# DAC.net
KiCad netlist of a schematic drawn in Altium Designer
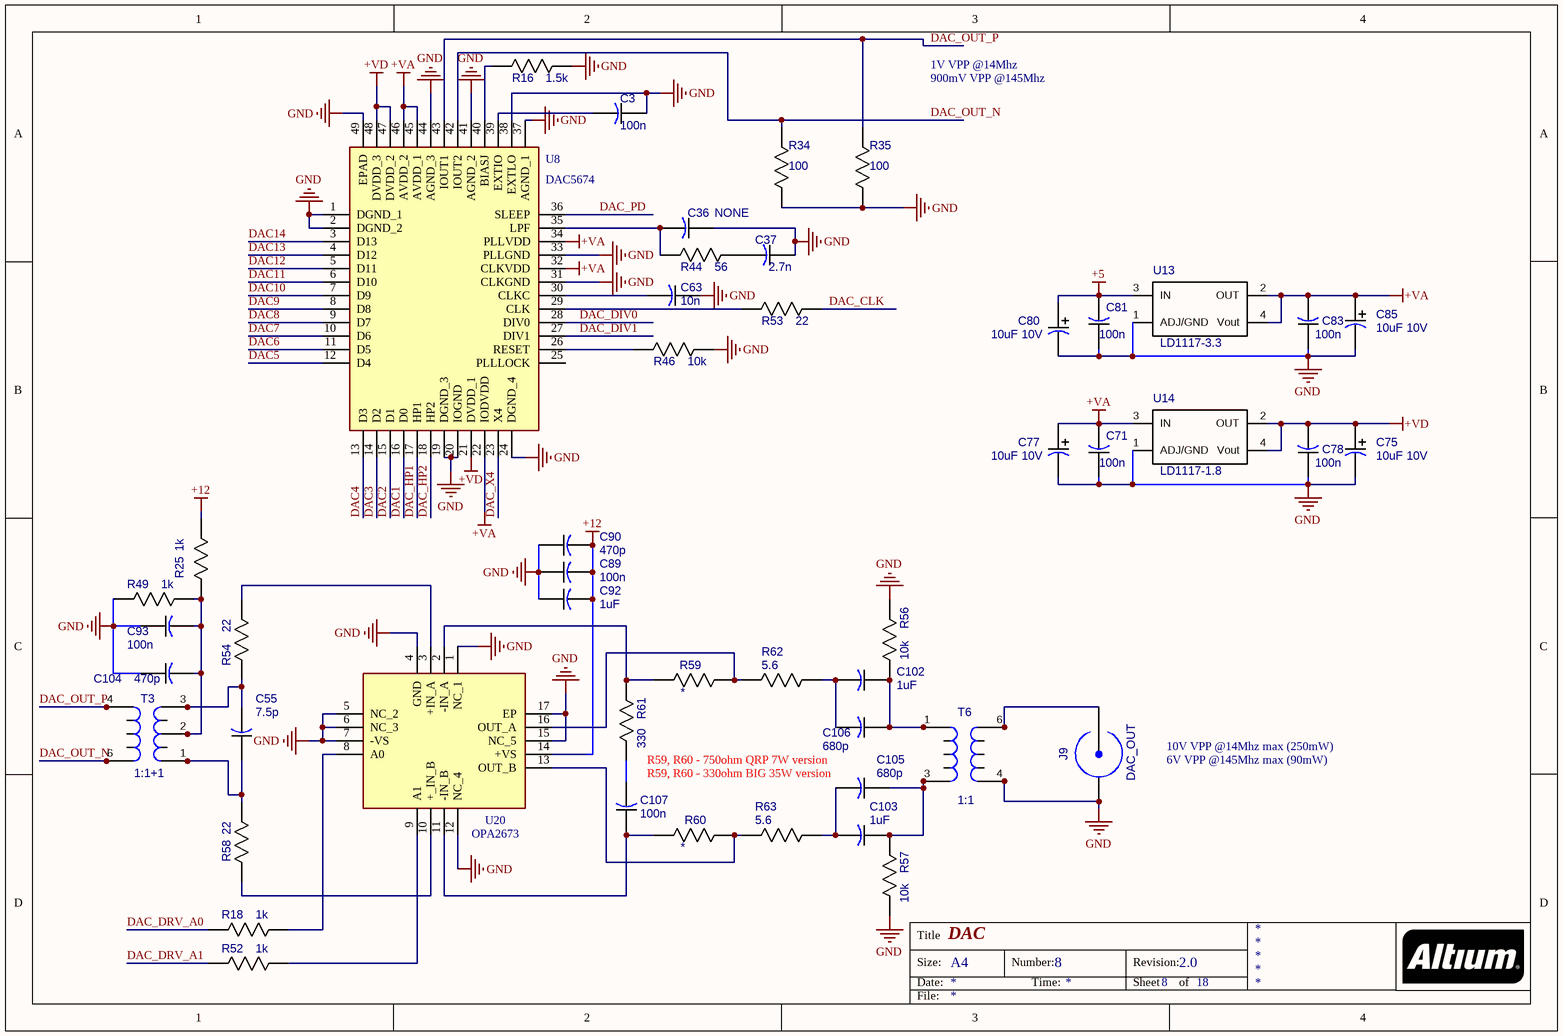
[diagram p0: DAC.SchDoc]

(export (version "E")
  (design (tool "Eeschema 10.0.6"))
  (components
    (comp (ref "C3")
      (value "100n")
      (footprint "CAP_0805")
      (description "CAP_0805")
      (libsource (lib "*") (part "CAP_0805"))
    )
    (comp (ref "C36")
      (value "NONE")
      (footprint "CAP_0805")
      (description "CAP_0805")
      (libsource (lib "*") (part "CAP_0805"))
    )
    (comp (ref "C37")
      (value "2.7n")
      (footprint "CAP_0805")
      (description "CAP_0805")
      (libsource (lib "*") (part "CAP_0805"))
    )
    (comp (ref "C55")
      (value "7.5p")
      (footprint "CAP_0805")
      (description "CAP_0805")
      (libsource (lib "*") (part "CAP_0805"))
    )
    (comp (ref "C63")
      (value "10n")
      (footprint "CAP_0805")
      (description "CAP_0805")
      (libsource (lib "*") (part "CAP_0805"))
    )
    (comp (ref "C71")
      (value "100n")
      (footprint "CAP_0805")
      (description "CAP_0805")
      (libsource (lib "*") (part "CAP_0805"))
    )
    (comp (ref "C75")
      (value "10uF 10V")
      (footprint "CAPAE_4.3x4.3h5.4")
      (description "CAPAE_4.3x4.3h5.4")
      (libsource (lib "MOTHERBOARD") (part "CAPAE_4.3x4.3h5.4"))
    )
    (comp (ref "C77")
      (value "10uF 10V")
      (footprint "CAPAE_4.3x4.3h5.4")
      (description "CAPAE_4.3x4.3h5.4")
      (libsource (lib "MOTHERBOARD") (part "CAPAE_4.3x4.3h5.4"))
    )
    (comp (ref "C78")
      (value "100n")
      (footprint "CAP_0805")
      (description "CAP_0805")
      (libsource (lib "*") (part "CAP_0805"))
    )
    (comp (ref "C80")
      (value "10uF 10V")
      (footprint "CAPAE_4.3x4.3h5.4")
      (description "CAPAE_4.3x4.3h5.4")
      (libsource (lib "MOTHERBOARD") (part "CAPAE_4.3x4.3h5.4"))
    )
    (comp (ref "C81")
      (value "100n")
      (footprint "CAP_0805")
      (description "CAP_0805")
      (libsource (lib "*") (part "CAP_0805"))
    )
    (comp (ref "C83")
      (value "100n")
      (footprint "CAP_0805")
      (description "CAP_0805")
      (libsource (lib "*") (part "CAP_0805"))
    )
    (comp (ref "C85")
      (value "10uF 10V")
      (footprint "CAPAE_4.3x4.3h5.4")
      (description "CAPAE_4.3x4.3h5.4")
      (libsource (lib "MOTHERBOARD") (part "CAPAE_4.3x4.3h5.4"))
    )
    (comp (ref "C89")
      (value "100n")
      (footprint "CAP_0805")
      (description "CAP_0805")
      (libsource (lib "*") (part "CAP_0805"))
    )
    (comp (ref "C90")
      (value "470p")
      (footprint "CAP_0805")
      (description "CAP_0805")
      (libsource (lib "*") (part "CAP_0805"))
    )
    (comp (ref "C92")
      (value "1uF")
      (footprint "CAP_0805")
      (description "CAP_0805")
      (libsource (lib "*") (part "CAP_0805"))
    )
    (comp (ref "C93")
      (value "100n")
      (footprint "CAP_0805")
      (description "CAP_0805")
      (libsource (lib "*") (part "CAP_0805"))
    )
    (comp (ref "C102")
      (value "1uF")
      (footprint "CAP_1206")
      (description "CAP_1206")
      (libsource (lib "*") (part "CAP_1206"))
    )
    (comp (ref "C103")
      (value "1uF")
      (footprint "CAP_1206")
      (description "CAP_1206")
      (libsource (lib "*") (part "CAP_1206"))
    )
    (comp (ref "C104")
      (value "470p")
      (footprint "CAP_0805")
      (description "CAP_0805")
      (libsource (lib "*") (part "CAP_0805"))
    )
    (comp (ref "C105")
      (value "680p")
      (footprint "CAP_1206")
      (description "CAP_1206")
      (libsource (lib "*") (part "CAP_1206"))
    )
    (comp (ref "C106")
      (value "680p")
      (footprint "CAP_1206")
      (description "CAP_1206")
      (libsource (lib "*") (part "CAP_1206"))
    )
    (comp (ref "C107")
      (value "100n")
      (footprint "CAP_0805")
      (description "CAP_0805")
      (libsource (lib "*") (part "CAP_0805"))
    )
    (comp (ref "J9")
      (value "DAC_OUT")
      (footprint "31-5431")
      (description "SMA")
      (libsource (lib "RF-UNIT_1") (part "31-5431"))
    )
    (comp (ref "R16")
      (value "1.5k")
      (footprint "RES_0805")
      (description "RES_0805")
      (libsource (lib "*") (part "RES_0805"))
    )
    (comp (ref "R18")
      (value "1k")
      (footprint "RES_0805")
      (description "RES_0805")
      (libsource (lib "*") (part "RES_0805"))
    )
    (comp (ref "R25")
      (value "1k")
      (footprint "RES_0805")
      (description "RES_0805")
      (libsource (lib "*") (part "RES_0805"))
    )
    (comp (ref "R34")
      (value "100")
      (footprint "RES_0805")
      (description "RES_0805")
      (libsource (lib "*") (part "RES_0805"))
    )
    (comp (ref "R35")
      (value "100")
      (footprint "RES_0805")
      (description "RES_0805")
      (libsource (lib "*") (part "RES_0805"))
    )
    (comp (ref "R44")
      (value "56")
      (footprint "RES_0805")
      (description "RES_0805")
      (libsource (lib "*") (part "RES_0805"))
    )
    (comp (ref "R46")
      (value "10k")
      (footprint "RES_0805")
      (description "RES_0805")
      (libsource (lib "*") (part "RES_0805"))
    )
    (comp (ref "R49")
      (value "1k")
      (footprint "RES_0805")
      (description "RES_0805")
      (libsource (lib "*") (part "RES_0805"))
    )
    (comp (ref "R52")
      (value "1k")
      (footprint "RES_0805")
      (description "RES_0805")
      (libsource (lib "*") (part "RES_0805"))
    )
    (comp (ref "R53")
      (value "22")
      (footprint "RES_0805")
      (description "RES_0805")
      (libsource (lib "*") (part "RES_0805"))
    )
    (comp (ref "R54")
      (value "22")
      (footprint "RES_0805")
      (description "RES_0805")
      (libsource (lib "*") (part "RES_0805"))
    )
    (comp (ref "R56")
      (value "10k")
      (footprint "RES_0805")
      (description "RES_0805")
      (libsource (lib "*") (part "RES_0805"))
    )
    (comp (ref "R57")
      (value "10k")
      (footprint "RES_0805")
      (description "RES_0805")
      (libsource (lib "*") (part "RES_0805"))
    )
    (comp (ref "R58")
      (value "22")
      (footprint "RES_0805")
      (description "RES_0805")
      (libsource (lib "*") (part "RES_0805"))
    )
    (comp (ref "R59")
      (value "*")
      (footprint "RES_0805")
      (description "RES_0805")
      (libsource (lib "*") (part "RES_0805"))
    )
    (comp (ref "R60")
      (value "*")
      (footprint "RES_0805")
      (description "RES_0805")
      (libsource (lib "*") (part "RES_0805"))
    )
    (comp (ref "R61")
      (value "330")
      (footprint "RES_0805")
      (description "RES_0805")
      (libsource (lib "*") (part "RES_0805"))
    )
    (comp (ref "R62")
      (value "5.6")
      (footprint "RES_1206")
      (description "RES_1206")
      (libsource (lib "*") (part "RES_1206"))
    )
    (comp (ref "R63")
      (value "5.6")
      (footprint "RES_1206")
      (description "RES_1206")
      (libsource (lib "*") (part "RES_1206"))
    )
    (comp (ref "T3")
      (value "1:1+1")
      (footprint "TRANSF_ACORE2")
      (description "Transformer")
      (libsource (lib "MOTHERBOARD_1") (part "TRANSF_ACORE2"))
    )
    (comp (ref "T6")
      (value "1:1")
      (footprint "TRANSF_ACORE")
      (description "Transformer")
      (libsource (lib "MOTHERBOARD_1") (part "TRANSF_ACORE"))
    )
    (comp (ref "U8")
      (value "DAC5674")
      (footprint "SamacSys:QFP50P900X900X100-49N")
      (description "Integrated Circuit")
      (fields (field (name "MANUFACTURER_PART_NUMBER") "DAC5674IPHP"))
      (libsource (lib "*") (part "DAC5674IPHP"))
    )
    (comp (ref "U13")
      (value "LD1117-3.3")
      (footprint "LT1117CST-3.3")
      (description "LT1117CST-3.3")
      (fields (field (name "Comment") "1117-3.3"))
      (libsource (lib "*") (part "LT1117CST-3.3"))
    )
    (comp (ref "U14")
      (value "LD1117-1.8")
      (footprint "LT1117CST-3.3")
      (description "LT1117CST-1.8")
      (fields (field (name "Comment") "1117-1.8"))
      (libsource (lib "*") (part "LT1117CST-3.3"))
    )
    (comp (ref "U20")
      (value "OPA2673")
      (footprint "SamacSys:QFN65P400X400X100-17N-D")
      (description "Integrated Circuit")
      (fields
        (field (name "MANUFACTURER_PART_NUMBER") "OPA2673IRGVT")
        (field (name "MOUSER PART NUMBER") "595-OPA2673IRGVT")
      )
      (libsource (lib "*") (part "OPA2673IRGVT"))
    )
  )
  (nets
    (net (code "1") (name "+5") (class "Default")
      (node (ref "C80") (pin "1") (pinfunction "PLUS_1") (pintype "passive"))
      (node (ref "C81") (pin "2") (pinfunction "2_2") (pintype "passive"))
      (node (ref "U13") (pin "3") (pinfunction "IN_3") (pintype "passive"))
    )
    (net (code "2") (name "+12") (class "Default")
      (node (ref "C89") (pin "2") (pinfunction "2_2") (pintype "passive"))
      (node (ref "C90") (pin "2") (pinfunction "2_2") (pintype "passive"))
      (node (ref "C92") (pin "2") (pinfunction "2_2") (pintype "passive"))
      (node (ref "R25") (pin "2") (pinfunction "2_2") (pintype "passive"))
      (node (ref "U20") (pin "14") (pinfunction "+VS_14") (pintype "passive"))
    )
    (net (code "3") (name "+VA") (class "Default")
      (node (ref "C71") (pin "2") (pinfunction "2_2") (pintype "passive"))
      (node (ref "C77") (pin "1") (pinfunction "PLUS_1") (pintype "passive"))
      (node (ref "C83") (pin "2") (pinfunction "2_2") (pintype "passive"))
      (node (ref "C85") (pin "1") (pinfunction "PLUS_1") (pintype "passive"))
      (node (ref "U13") (pin "2") (pinfunction "OUT_2") (pintype "passive"))
      (node (ref "U13") (pin "4") (pinfunction "Vout_4") (pintype "passive"))
      (node (ref "U14") (pin "3") (pinfunction "IN_3") (pintype "passive"))
      (node (ref "U8") (pin "22") (pinfunction "IODVDD_22") (pintype "passive"))
      (node (ref "U8") (pin "32") (pinfunction "CLKVDD_32") (pintype "passive"))
      (node (ref "U8") (pin "34") (pinfunction "PLLVDD_34") (pintype "passive"))
      (node (ref "U8") (pin "45") (pinfunction "AVDD_1_45") (pintype "passive"))
      (node (ref "U8") (pin "46") (pinfunction "AVDD_2_46") (pintype "passive"))
    )
    (net (code "4") (name "+VD") (class "Default")
      (node (ref "C75") (pin "1") (pinfunction "PLUS_1") (pintype "passive"))
      (node (ref "C78") (pin "2") (pinfunction "2_2") (pintype "passive"))
      (node (ref "U14") (pin "2") (pinfunction "OUT_2") (pintype "passive"))
      (node (ref "U14") (pin "4") (pinfunction "Vout_4") (pintype "passive"))
      (node (ref "U8") (pin "21") (pinfunction "DVDD_1_21") (pintype "passive"))
      (node (ref "U8") (pin "47") (pinfunction "DVDD_2_47") (pintype "passive"))
      (node (ref "U8") (pin "48") (pinfunction "DVDD_3_48") (pintype "passive"))
    )
    (net (code "5") (name "/DAC1") (class "Default")
      (node (ref "U8") (pin "16") (pinfunction "D0_16") (pintype "passive"))
    )
    (net (code "6") (name "/DAC2") (class "Default")
      (node (ref "U8") (pin "15") (pinfunction "D1_15") (pintype "passive"))
    )
    (net (code "7") (name "/DAC3") (class "Default")
      (node (ref "U8") (pin "14") (pinfunction "D2_14") (pintype "passive"))
    )
    (net (code "8") (name "/DAC4") (class "Default")
      (node (ref "U8") (pin "13") (pinfunction "D3_13") (pintype "passive"))
    )
    (net (code "9") (name "/DAC5") (class "Default")
      (node (ref "U8") (pin "12") (pinfunction "D4_12") (pintype "passive"))
    )
    (net (code "10") (name "/DAC6") (class "Default")
      (node (ref "U8") (pin "11") (pinfunction "D5_11") (pintype "passive"))
    )
    (net (code "11") (name "/DAC7") (class "Default")
      (node (ref "U8") (pin "10") (pinfunction "D6_10") (pintype "passive"))
    )
    (net (code "12") (name "/DAC8") (class "Default")
      (node (ref "U8") (pin "9") (pinfunction "D7_9") (pintype "passive"))
    )
    (net (code "13") (name "/DAC9") (class "Default")
      (node (ref "U8") (pin "8") (pinfunction "D8_8") (pintype "passive"))
    )
    (net (code "14") (name "/DAC10") (class "Default")
      (node (ref "U8") (pin "7") (pinfunction "D9_7") (pintype "passive"))
    )
    (net (code "15") (name "/DAC11") (class "Default")
      (node (ref "U8") (pin "6") (pinfunction "D10_6") (pintype "passive"))
    )
    (net (code "16") (name "/DAC12") (class "Default")
      (node (ref "U8") (pin "5") (pinfunction "D11_5") (pintype "passive"))
    )
    (net (code "17") (name "/DAC13") (class "Default")
      (node (ref "U8") (pin "4") (pinfunction "D12_4") (pintype "passive"))
    )
    (net (code "18") (name "/DAC14") (class "Default")
      (node (ref "U8") (pin "3") (pinfunction "D13_3") (pintype "passive"))
    )
    (net (code "19") (name "/DAC_CLK") (class "Default")
      (node (ref "R53") (pin "1") (pinfunction "1_1") (pintype "passive"))
    )
    (net (code "20") (name "/DAC_DIV0") (class "Default")
      (node (ref "U8") (pin "28") (pinfunction "DIV0_28") (pintype "passive"))
    )
    (net (code "21") (name "/DAC_DIV1") (class "Default")
      (node (ref "U8") (pin "27") (pinfunction "DIV1_27") (pintype "passive"))
    )
    (net (code "22") (name "/DAC_DRV_A0") (class "Default")
      (node (ref "R18") (pin "1") (pinfunction "1_1") (pintype "passive"))
    )
    (net (code "23") (name "/DAC_DRV_A1") (class "Default")
      (node (ref "R52") (pin "1") (pinfunction "1_1") (pintype "passive"))
    )
    (net (code "24") (name "/DAC_HP1") (class "Default")
      (node (ref "U8") (pin "17") (pinfunction "HP1_17") (pintype "passive"))
    )
    (net (code "25") (name "/DAC_HP2") (class "Default")
      (node (ref "U8") (pin "18") (pinfunction "HP2_18") (pintype "passive"))
    )
    (net (code "26") (name "/DAC_OUT_N") (class "Default")
      (node (ref "R34") (pin "2") (pinfunction "2_2") (pintype "passive"))
      (node (ref "T3") (pin "10") (pinfunction "0_10") (pintype "passive"))
      (node (ref "T3") (pin "6") (pinfunction "P2_6") (pintype "passive"))
      (node (ref "U8") (pin "42") (pinfunction "IOUT2_42") (pintype "passive"))
    )
    (net (code "27") (name "/DAC_OUT_P") (class "Default")
      (node (ref "R35") (pin "2") (pinfunction "2_2") (pintype "passive"))
      (node (ref "T3") (pin "11") (pinfunction "0_11") (pintype "passive"))
      (node (ref "T3") (pin "4") (pinfunction "P1_4") (pintype "passive"))
      (node (ref "U8") (pin "43") (pinfunction "IOUT1_43") (pintype "passive"))
    )
    (net (code "28") (name "/DAC_PD") (class "Default")
      (node (ref "U8") (pin "36") (pinfunction "SLEEP_36") (pintype "passive"))
    )
    (net (code "29") (name "/DAC_X4") (class "Default")
      (node (ref "U8") (pin "23") (pinfunction "X4_23") (pintype "passive"))
    )
    (net (code "30") (name "GND") (class "Default")
      (node (ref "C104") (pin "1") (pinfunction "1_1") (pintype "passive"))
      (node (ref "C3") (pin "1") (pinfunction "1_1") (pintype "passive"))
      (node (ref "C36") (pin "1") (pinfunction "1_1") (pintype "passive"))
      (node (ref "C37") (pin "1") (pinfunction "1_1") (pintype "passive"))
      (node (ref "C63") (pin "1") (pinfunction "1_1") (pintype "passive"))
      (node (ref "C71") (pin "1") (pinfunction "1_1") (pintype "passive"))
      (node (ref "C75") (pin "2") (pinfunction "MINUS_2") (pintype "passive"))
      (node (ref "C77") (pin "2") (pinfunction "MINUS_2") (pintype "passive"))
      (node (ref "C78") (pin "1") (pinfunction "1_1") (pintype "passive"))
      (node (ref "C80") (pin "2") (pinfunction "MINUS_2") (pintype "passive"))
      (node (ref "C81") (pin "1") (pinfunction "1_1") (pintype "passive"))
      (node (ref "C83") (pin "1") (pinfunction "1_1") (pintype "passive"))
      (node (ref "C85") (pin "2") (pinfunction "MINUS_2") (pintype "passive"))
      (node (ref "C89") (pin "1") (pinfunction "1_1") (pintype "passive"))
      (node (ref "C90") (pin "1") (pinfunction "1_1") (pintype "passive"))
      (node (ref "C92") (pin "1") (pinfunction "1_1") (pintype "passive"))
      (node (ref "C93") (pin "1") (pinfunction "1_1") (pintype "passive"))
      (node (ref "J9") (pin "1") (pinfunction "GND_1") (pintype "passive"))
      (node (ref "J9") (pin "2") (pinfunction "GND_2") (pintype "passive"))
      (node (ref "J9") (pin "3") (pinfunction "GND_3") (pintype "passive"))
      (node (ref "J9") (pin "4") (pinfunction "GND_4") (pintype "passive"))
      (node (ref "R16") (pin "1") (pinfunction "1_1") (pintype "passive"))
      (node (ref "R34") (pin "1") (pinfunction "1_1") (pintype "passive"))
      (node (ref "R35") (pin "1") (pinfunction "1_1") (pintype "passive"))
      (node (ref "R46") (pin "1") (pinfunction "1_1") (pintype "passive"))
      (node (ref "R49") (pin "2") (pinfunction "2_2") (pintype "passive"))
      (node (ref "R56") (pin "1") (pinfunction "1_1") (pintype "passive"))
      (node (ref "R57") (pin "2") (pinfunction "2_2") (pintype "passive"))
      (node (ref "T6") (pin "11") (pinfunction "0_11") (pintype "passive"))
      (node (ref "T6") (pin "4") (pinfunction "S2_4") (pintype "passive"))
      (node (ref "U13") (pin "1") (pinfunction "ADJ/GND_1") (pintype "passive"))
      (node (ref "U14") (pin "1") (pinfunction "ADJ/GND_1") (pintype "passive"))
      (node (ref "U20") (pin "1") (pinfunction "NC_1_1") (pintype "passive"))
      (node (ref "U20") (pin "12") (pinfunction "NC_4_12") (pintype "passive"))
      (node (ref "U20") (pin "15") (pinfunction "NC_5_15") (pintype "passive"))
      (node (ref "U20") (pin "17") (pinfunction "EP_17") (pintype "passive"))
      (node (ref "U20") (pin "4") (pinfunction "GND_4") (pintype "passive"))
      (node (ref "U20") (pin "5") (pinfunction "NC_2_5") (pintype "passive"))
      (node (ref "U20") (pin "6") (pinfunction "NC_3_6") (pintype "passive"))
      (node (ref "U20") (pin "7") (pinfunction "-VS_7") (pintype "passive"))
      (node (ref "U8") (pin "1") (pinfunction "DGND_1_1") (pintype "passive"))
      (node (ref "U8") (pin "19") (pinfunction "DGND_3_19") (pintype "passive"))
      (node (ref "U8") (pin "2") (pinfunction "DGND_2_2") (pintype "passive"))
      (node (ref "U8") (pin "20") (pinfunction "IOGND_20") (pintype "passive"))
      (node (ref "U8") (pin "24") (pinfunction "DGND_4_24") (pintype "passive"))
      (node (ref "U8") (pin "31") (pinfunction "CLKGND_31") (pintype "passive"))
      (node (ref "U8") (pin "33") (pinfunction "PLLGND_33") (pintype "passive"))
      (node (ref "U8") (pin "37") (pinfunction "AGND_1_37") (pintype "passive"))
      (node (ref "U8") (pin "38") (pinfunction "EXTLO_38") (pintype "passive"))
      (node (ref "U8") (pin "41") (pinfunction "AGND_2_41") (pintype "passive"))
      (node (ref "U8") (pin "44") (pinfunction "AGND_3_44") (pintype "passive"))
      (node (ref "U8") (pin "49") (pinfunction "EPAD_49") (pintype "passive"))
    )
    (net (code "31") (name "Net-(C37-Pad2)") (class "Default")
      (node (ref "C37") (pin "2") (pinfunction "2_2") (pintype "passive"))
      (node (ref "R44") (pin "1") (pinfunction "1_1") (pintype "passive"))
    )
    (net (code "32") (name "Net-(C102-Pad2)") (class "Default")
      (node (ref "C102") (pin "2") (pinfunction "2_2") (pintype "passive"))
      (node (ref "C106") (pin "2") (pinfunction "2_2") (pintype "passive"))
      (node (ref "R62") (pin "1") (pinfunction "1_1") (pintype "passive"))
    )
    (net (code "33") (name "Net-(C103-Pad2)") (class "Default")
      (node (ref "C103") (pin "2") (pinfunction "2_2") (pintype "passive"))
      (node (ref "C105") (pin "2") (pinfunction "2_2") (pintype "passive"))
      (node (ref "R63") (pin "1") (pinfunction "1_1") (pintype "passive"))
    )
    (net (code "34") (name "Net-(C107-Pad2)") (class "Default")
      (node (ref "C107") (pin "2") (pinfunction "2_2") (pintype "passive"))
      (node (ref "R61") (pin "2") (pinfunction "2_2") (pintype "passive"))
    )
    (net (code "35") (name "Net-(J9-CON)") (class "Default")
      (node (ref "J9") (pin "5") (pinfunction "CON_5") (pintype "passive"))
      (node (ref "T6") (pin "10") (pinfunction "0_10") (pintype "passive"))
      (node (ref "T6") (pin "6") (pinfunction "S1_6") (pintype "passive"))
    )
    (net (code "36") (name "Net-(T3-S1)") (class "Default")
      (node (ref "C55") (pin "2") (pinfunction "2_2") (pintype "passive"))
      (node (ref "R54") (pin "1") (pinfunction "1_1") (pintype "passive"))
      (node (ref "T3") (pin "3") (pinfunction "S1_3") (pintype "passive"))
      (node (ref "T3") (pin "9") (pinfunction "0_9") (pintype "passive"))
    )
    (net (code "37") (name "Net-(T3-S2)") (class "Default")
      (node (ref "C104") (pin "2") (pinfunction "2_2") (pintype "passive"))
      (node (ref "C93") (pin "2") (pinfunction "2_2") (pintype "passive"))
      (node (ref "R25") (pin "1") (pinfunction "1_1") (pintype "passive"))
      (node (ref "R49") (pin "1") (pinfunction "1_1") (pintype "passive"))
      (node (ref "T3") (pin "2") (pinfunction "S2_2") (pintype "passive"))
      (node (ref "T3") (pin "8") (pinfunction "0_8") (pintype "passive"))
    )
    (net (code "38") (name "Net-(T3-S3)") (class "Default")
      (node (ref "C55") (pin "1") (pinfunction "1_1") (pintype "passive"))
      (node (ref "R58") (pin "2") (pinfunction "2_2") (pintype "passive"))
      (node (ref "T3") (pin "1") (pinfunction "S3_1") (pintype "passive"))
      (node (ref "T3") (pin "7") (pinfunction "0_7") (pintype "passive"))
    )
    (net (code "39") (name "Net-(T6-P1)") (class "Default")
      (node (ref "C102") (pin "1") (pinfunction "1_1") (pintype "passive"))
      (node (ref "C106") (pin "1") (pinfunction "1_1") (pintype "passive"))
      (node (ref "R56") (pin "2") (pinfunction "2_2") (pintype "passive"))
      (node (ref "T6") (pin "1") (pinfunction "P1_1") (pintype "passive"))
      (node (ref "T6") (pin "7") (pinfunction "0_7") (pintype "passive"))
    )
    (net (code "40") (name "Net-(T6-P2)") (class "Default")
      (node (ref "C103") (pin "1") (pinfunction "1_1") (pintype "passive"))
      (node (ref "C105") (pin "1") (pinfunction "1_1") (pintype "passive"))
      (node (ref "R57") (pin "1") (pinfunction "1_1") (pintype "passive"))
      (node (ref "T6") (pin "3") (pinfunction "P2_3") (pintype "passive"))
      (node (ref "T6") (pin "9") (pinfunction "0_9") (pintype "passive"))
    )
    (net (code "41") (name "Net-(U8-BIASJ)") (class "Default")
      (node (ref "R16") (pin "2") (pinfunction "2_2") (pintype "passive"))
      (node (ref "U8") (pin "40") (pinfunction "BIASJ_40") (pintype "passive"))
    )
    (net (code "42") (name "Net-(U8-CLK)") (class "Default")
      (node (ref "R53") (pin "2") (pinfunction "2_2") (pintype "passive"))
      (node (ref "U8") (pin "29") (pinfunction "CLK_29") (pintype "passive"))
    )
    (net (code "43") (name "Net-(U8-CLKC)") (class "Default")
      (node (ref "C63") (pin "2") (pinfunction "2_2") (pintype "passive"))
      (node (ref "U8") (pin "30") (pinfunction "CLKC_30") (pintype "passive"))
    )
    (net (code "44") (name "Net-(U8-EXTIO)") (class "Default")
      (node (ref "C3") (pin "2") (pinfunction "2_2") (pintype "passive"))
      (node (ref "U8") (pin "39") (pinfunction "EXTIO_39") (pintype "passive"))
    )
    (net (code "45") (name "Net-(U8-LPF)") (class "Default")
      (node (ref "C36") (pin "2") (pinfunction "2_2") (pintype "passive"))
      (node (ref "R44") (pin "2") (pinfunction "2_2") (pintype "passive"))
      (node (ref "U8") (pin "35") (pinfunction "LPF_35") (pintype "passive"))
    )
    (net (code "46") (name "Net-(U8-RESET)") (class "Default")
      (node (ref "R46") (pin "2") (pinfunction "2_2") (pintype "passive"))
      (node (ref "U8") (pin "26") (pinfunction "RESET_26") (pintype "passive"))
    )
    (net (code "47") (name "Net-(U20-+IN_A)") (class "Default")
      (node (ref "R54") (pin "2") (pinfunction "2_2") (pintype "passive"))
      (node (ref "U20") (pin "3") (pinfunction "+IN_A_3") (pintype "passive"))
    )
    (net (code "48") (name "Net-(U20-+_IN_B)") (class "Default")
      (node (ref "R58") (pin "1") (pinfunction "1_1") (pintype "passive"))
      (node (ref "U20") (pin "10") (pinfunction "+_IN_B_10") (pintype "passive"))
    )
    (net (code "49") (name "Net-(U20--IN_A)") (class "Default")
      (node (ref "R59") (pin "2") (pinfunction "2_2") (pintype "passive"))
      (node (ref "R61") (pin "1") (pinfunction "1_1") (pintype "passive"))
      (node (ref "U20") (pin "2") (pinfunction "-IN_A_2") (pintype "passive"))
    )
    (net (code "50") (name "Net-(U20--IN_B)") (class "Default")
      (node (ref "C107") (pin "1") (pinfunction "1_1") (pintype "passive"))
      (node (ref "R60") (pin "2") (pinfunction "2_2") (pintype "passive"))
      (node (ref "U20") (pin "11") (pinfunction "-IN_B_11") (pintype "passive"))
    )
    (net (code "51") (name "Net-(U20-A0)") (class "Default")
      (node (ref "R18") (pin "2") (pinfunction "2_2") (pintype "passive"))
      (node (ref "U20") (pin "8") (pinfunction "A0_8") (pintype "passive"))
    )
    (net (code "52") (name "Net-(U20-A1)") (class "Default")
      (node (ref "R52") (pin "2") (pinfunction "2_2") (pintype "passive"))
      (node (ref "U20") (pin "9") (pinfunction "A1_9") (pintype "passive"))
    )
    (net (code "53") (name "Net-(U20-OUT_A)") (class "Default")
      (node (ref "R59") (pin "1") (pinfunction "1_1") (pintype "passive"))
      (node (ref "R62") (pin "2") (pinfunction "2_2") (pintype "passive"))
      (node (ref "U20") (pin "16") (pinfunction "OUT_A_16") (pintype "passive"))
    )
    (net (code "54") (name "Net-(U20-OUT_B)") (class "Default")
      (node (ref "R60") (pin "1") (pinfunction "1_1") (pintype "passive"))
      (node (ref "R63") (pin "2") (pinfunction "2_2") (pintype "passive"))
      (node (ref "U20") (pin "13") (pinfunction "OUT_B_13") (pintype "passive"))
    )
    (net (code "55") (name "unconnected-(T6-0-Pad8)") (class "Default")
      (node (ref "T6") (pin "8") (pinfunction "0_8") (pintype "passive"))
    )
    (net (code "56") (name "unconnected-(U8-PLLLOCK-Pad25)") (class "Default")
      (node (ref "U8") (pin "25") (pinfunction "PLLLOCK_25") (pintype "passive"))
    )
  )
)
